# Super_iO_board.net
KiCad netlist of a schematic drawn in EAGLE
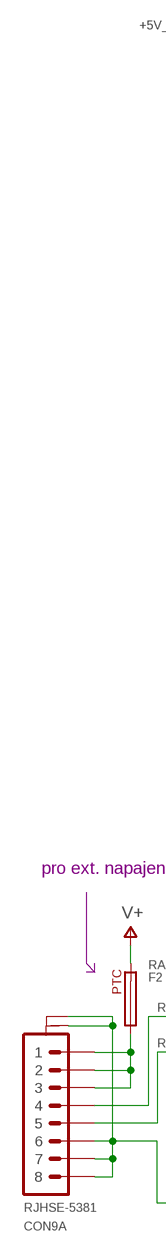
[diagram p0: schematic, sheet 1, part 1 of 2]
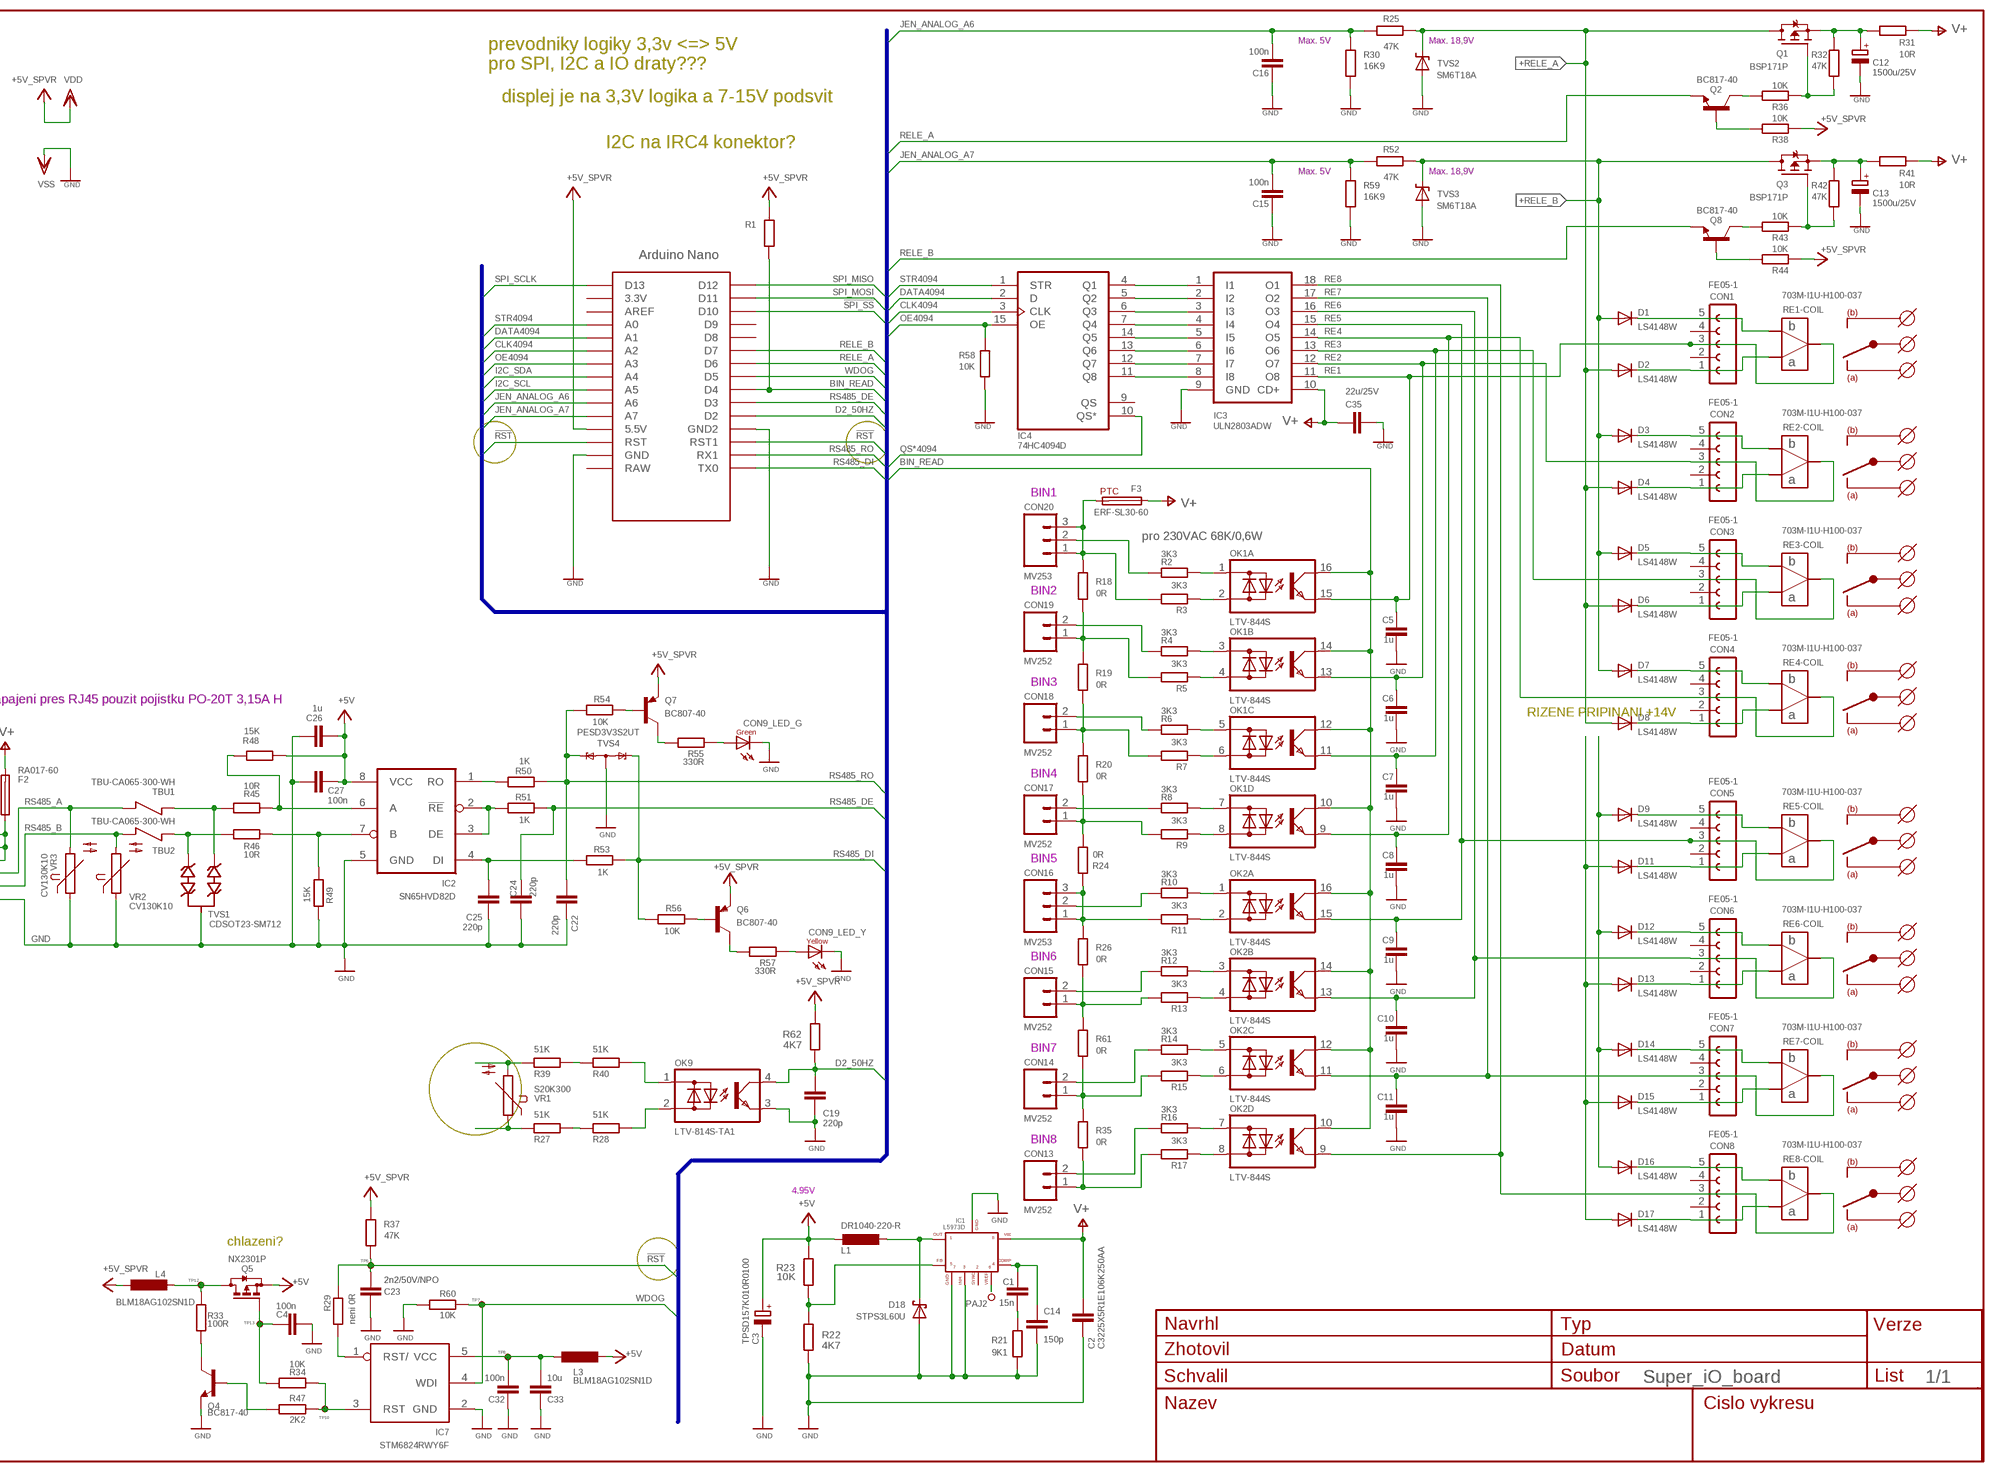
[diagram p1: schematic, sheet 1, part 2 of 2]

(export (version "E")
  (design (tool "Eeschema 10.0.6"))
  (components
    (comp (ref "C1")
      (value "15n")
      (footprint "eagle-import:C0805C")
      (libsource (lib "eagle-import") (part "C_EU_C0805C"))
    )
    (comp (ref "C2")
      (value "C3225X5R1E106K250AA")
      (footprint "eagle-import:C1210")
      (libsource (lib "eagle-import") (part "C-EUC1210"))
    )
    (comp (ref "C3")
      (value "TPSD157K010R0100")
      (footprint "eagle-import:D_7343-31R")
      (libsource (lib "eagle-import") (part "CPOL-EUD/7343-31R"))
    )
    (comp (ref "C4")
      (value "100n")
      (footprint "eagle-import:C0805C-M")
      (libsource (lib "eagle-import") (part "C_EU_C0805C-M"))
    )
    (comp (ref "C5")
      (value "1u")
      (footprint "eagle-import:C0805C-M")
      (libsource (lib "eagle-import") (part "C_EU_C0805C-M"))
    )
    (comp (ref "C6")
      (value "1u")
      (footprint "eagle-import:C0805C-M")
      (libsource (lib "eagle-import") (part "C_EU_C0805C-M"))
    )
    (comp (ref "C7")
      (value "1u")
      (footprint "eagle-import:C0805C-M")
      (libsource (lib "eagle-import") (part "C_EU_C0805C-M"))
    )
    (comp (ref "C8")
      (value "1u")
      (footprint "eagle-import:C0805C-M")
      (libsource (lib "eagle-import") (part "C_EU_C0805C-M"))
    )
    (comp (ref "C9")
      (value "1u")
      (footprint "eagle-import:C0805C-M")
      (libsource (lib "eagle-import") (part "C_EU_C0805C-M"))
    )
    (comp (ref "C10")
      (value "1u")
      (footprint "eagle-import:C0805C-M")
      (libsource (lib "eagle-import") (part "C_EU_C0805C-M"))
    )
    (comp (ref "C11")
      (value "1u")
      (footprint "eagle-import:C0805C-M")
      (libsource (lib "eagle-import") (part "C_EU_C0805C-M"))
    )
    (comp (ref "C12")
      (value "1500u/25V")
      (footprint "eagle-import:E5-13")
      (libsource (lib "eagle-import") (part "CPOL-EUE5-13"))
    )
    (comp (ref "C13")
      (value "1500u/25V")
      (footprint "eagle-import:E5-13")
      (libsource (lib "eagle-import") (part "CPOL-EUE5-13"))
    )
    (comp (ref "C14")
      (value "150p")
      (footprint "eagle-import:C0805C")
      (libsource (lib "eagle-import") (part "C_EU_C0805C"))
    )
    (comp (ref "C15")
      (value "100n")
      (footprint "eagle-import:C0805C-M")
      (libsource (lib "eagle-import") (part "C_EU_C0805C-M"))
    )
    (comp (ref "C16")
      (value "100n")
      (footprint "eagle-import:C0805C-M")
      (libsource (lib "eagle-import") (part "C_EU_C0805C-M"))
    )
    (comp (ref "C19")
      (value "220p")
      (footprint "eagle-import:C0805C-M")
      (libsource (lib "eagle-import") (part "C_EU_C0805C-M"))
    )
    (comp (ref "C22")
      (value "220p")
      (footprint "eagle-import:C0805C-M")
      (libsource (lib "eagle-import") (part "C_EU_C0805C-M"))
    )
    (comp (ref "C23")
      (value "2n2/50V/NPO")
      (footprint "eagle-import:C0805C-M")
      (libsource (lib "eagle-import") (part "C_EU_C0805C-M"))
    )
    (comp (ref "C24")
      (value "220p")
      (footprint "eagle-import:C0805C-M")
      (libsource (lib "eagle-import") (part "C_EU_C0805C-M"))
    )
    (comp (ref "C25")
      (value "220p")
      (footprint "eagle-import:C0805C-M")
      (libsource (lib "eagle-import") (part "C_EU_C0805C-M"))
    )
    (comp (ref "C26")
      (value "1u")
      (footprint "eagle-import:C0805C-M")
      (libsource (lib "eagle-import") (part "C_EU_C0805C-M"))
    )
    (comp (ref "C27")
      (value "100n")
      (footprint "eagle-import:C0805C-M")
      (libsource (lib "eagle-import") (part "C_EU_C0805C-M"))
    )
    (comp (ref "C32")
      (value "100n")
      (footprint "eagle-import:C0805C-M")
      (libsource (lib "eagle-import") (part "C_EU_C0805C-M"))
    )
    (comp (ref "C33")
      (value "10u")
      (footprint "eagle-import:C0805C-M")
      (libsource (lib "eagle-import") (part "C_EU_C0805C-M"))
    )
    (comp (ref "C35")
      (value "22u/25V")
      (footprint "eagle-import:C1206")
      (libsource (lib "eagle-import") (part "C_EU_1206"))
    )
    (comp (ref "CON1")
      (value "FE05-1")
      (footprint "eagle-import:FE05-1")
      (libsource (lib "eagle-import") (part "FE05-1"))
    )
    (comp (ref "CON2")
      (value "FE05-1")
      (footprint "eagle-import:FE05-1")
      (libsource (lib "eagle-import") (part "FE05-1"))
    )
    (comp (ref "CON3")
      (value "FE05-1")
      (footprint "eagle-import:FE05-1")
      (libsource (lib "eagle-import") (part "FE05-1"))
    )
    (comp (ref "CON4")
      (value "FE05-1")
      (footprint "eagle-import:FE05-1")
      (libsource (lib "eagle-import") (part "FE05-1"))
    )
    (comp (ref "CON5")
      (value "FE05-1")
      (footprint "eagle-import:FE05-1")
      (libsource (lib "eagle-import") (part "FE05-1"))
    )
    (comp (ref "CON6")
      (value "FE05-1")
      (footprint "eagle-import:FE05-1")
      (libsource (lib "eagle-import") (part "FE05-1"))
    )
    (comp (ref "CON7")
      (value "FE05-1")
      (footprint "eagle-import:FE05-1")
      (libsource (lib "eagle-import") (part "FE05-1"))
    )
    (comp (ref "CON8")
      (value "FE05-1")
      (footprint "eagle-import:FE05-1")
      (libsource (lib "eagle-import") (part "FE05-1"))
    )
    (comp (ref "CON9")
      (value "RJHSE-5381")
      (footprint "eagle-import:RJHSE538X_PROKOVY")
      (libsource (lib "eagle-import") (part "RJHSE5381_PROKOVY"))
    )
    (comp (ref "CON13")
      (value "MV252")
      (footprint "eagle-import:MRT5_2_61010-1_KULATE")
      (libsource (lib "eagle-import") (part "MRT5_2_61010-1_KULATE"))
    )
    (comp (ref "CON14")
      (value "MV252")
      (footprint "eagle-import:MRT5_2_61010-1_KULATE")
      (libsource (lib "eagle-import") (part "MRT5_2_61010-1_KULATE"))
    )
    (comp (ref "CON15")
      (value "MV252")
      (footprint "eagle-import:MRT5_2_61010-1_KULATE")
      (libsource (lib "eagle-import") (part "MRT5_2_61010-1_KULATE"))
    )
    (comp (ref "CON16")
      (value "MV253")
      (footprint "eagle-import:MRT5_3_61010-1_KULATE")
      (libsource (lib "eagle-import") (part "MRT5_3_61010-1_KULATE"))
    )
    (comp (ref "CON17")
      (value "MV252")
      (footprint "eagle-import:MRT5_2_61010-1_KULATE")
      (libsource (lib "eagle-import") (part "MRT5_2_61010-1_KULATE"))
    )
    (comp (ref "CON18")
      (value "MV252")
      (footprint "eagle-import:MRT5_2_61010-1_KULATE")
      (libsource (lib "eagle-import") (part "MRT5_2_61010-1_KULATE"))
    )
    (comp (ref "CON19")
      (value "MV252")
      (footprint "eagle-import:MRT5_2_61010-1_KULATE")
      (libsource (lib "eagle-import") (part "MRT5_2_61010-1_KULATE"))
    )
    (comp (ref "CON20")
      (value "MV253")
      (footprint "eagle-import:MRT5_3_61010-1_KULATE")
      (libsource (lib "eagle-import") (part "MRT5_3_61010-1_KULATE"))
    )
    (comp (ref "D1")
      (value "LS4148W")
      (footprint "eagle-import:D1206")
      (libsource (lib "eagle-import") (part "1N41481206"))
    )
    (comp (ref "D2")
      (value "LS4148W")
      (footprint "eagle-import:D1206")
      (libsource (lib "eagle-import") (part "1N41481206"))
    )
    (comp (ref "D3")
      (value "LS4148W")
      (footprint "eagle-import:D1206")
      (libsource (lib "eagle-import") (part "1N41481206"))
    )
    (comp (ref "D4")
      (value "LS4148W")
      (footprint "eagle-import:D1206")
      (libsource (lib "eagle-import") (part "1N41481206"))
    )
    (comp (ref "D5")
      (value "LS4148W")
      (footprint "eagle-import:D1206")
      (libsource (lib "eagle-import") (part "1N41481206"))
    )
    (comp (ref "D6")
      (value "LS4148W")
      (footprint "eagle-import:D1206")
      (libsource (lib "eagle-import") (part "1N41481206"))
    )
    (comp (ref "D7")
      (value "LS4148W")
      (footprint "eagle-import:D1206")
      (libsource (lib "eagle-import") (part "1N41481206"))
    )
    (comp (ref "D8")
      (value "LS4148W")
      (footprint "eagle-import:D1206")
      (libsource (lib "eagle-import") (part "1N41481206"))
    )
    (comp (ref "D9")
      (value "LS4148W")
      (footprint "eagle-import:D1206")
      (libsource (lib "eagle-import") (part "1N41481206"))
    )
    (comp (ref "D11")
      (value "LS4148W")
      (footprint "eagle-import:D1206")
      (libsource (lib "eagle-import") (part "1N41481206"))
    )
    (comp (ref "D12")
      (value "LS4148W")
      (footprint "eagle-import:D1206")
      (libsource (lib "eagle-import") (part "1N41481206"))
    )
    (comp (ref "D13")
      (value "LS4148W")
      (footprint "eagle-import:D1206")
      (libsource (lib "eagle-import") (part "1N41481206"))
    )
    (comp (ref "D14")
      (value "LS4148W")
      (footprint "eagle-import:D1206")
      (libsource (lib "eagle-import") (part "1N41481206"))
    )
    (comp (ref "D15")
      (value "LS4148W")
      (footprint "eagle-import:D1206")
      (libsource (lib "eagle-import") (part "1N41481206"))
    )
    (comp (ref "D16")
      (value "LS4148W")
      (footprint "eagle-import:D1206")
      (libsource (lib "eagle-import") (part "1N41481206"))
    )
    (comp (ref "D17")
      (value "LS4148W")
      (footprint "eagle-import:D1206")
      (libsource (lib "eagle-import") (part "1N41481206"))
    )
    (comp (ref "D18")
      (value "STPS3L60U")
      (footprint "eagle-import:SMB")
      (libsource (lib "eagle-import") (part "SCHOTTKY-DIODESMD"))
    )
    (comp (ref "F2")
      (value "RA017-60")
      (footprint "eagle-import:ERF-RA01760Z")
      (libsource (lib "eagle-import") (part "RA017-60017-60"))
    )
    (comp (ref "F3")
      (value "ERF-SL30-60")
      (footprint "eagle-import:ERF-SL030")
      (libsource (lib "eagle-import") (part "ERF-SL030-60"))
    )
    (comp (ref "IC1")
      (value "L5973D")
      (footprint "eagle-import:HSOP8")
      (libsource (lib "eagle-import") (part "L5973D"))
    )
    (comp (ref "IC2")
      (value "SN65HVD82D")
      (footprint "eagle-import:SO8_IPC_LEPIDLO")
      (libsource (lib "eagle-import") (part "ISL8487LEPIDLO"))
    )
    (comp (ref "IC3")
      (value "ULN2803ADW")
      (footprint "eagle-import:SO18W")
      (libsource (lib "eagle-import") (part "ULN2803ASMD"))
    )
    (comp (ref "IC4")
      (value "74HC4094D")
      (footprint "eagle-import:SO16")
      (libsource (lib "eagle-import") (part "4094D"))
    )
    (comp (ref "IC7")
      (value "STM6824RWY6F")
      (footprint "eagle-import:SOT23-5L")
      (libsource (lib "eagle-import") (part "STM6824SOT23-5L"))
    )
    (comp (ref "L1")
      (value "DR1040-220-R")
      (footprint "eagle-import:DR1040_RUCNE")
      (libsource (lib "eagle-import") (part "L-EUDR1040_RUCNE"))
    )
    (comp (ref "L3")
      (value "BLM18AG102SN1D")
      (footprint "eagle-import:L0603")
      (libsource (lib "eagle-import") (part "L-EUL0603"))
    )
    (comp (ref "L4")
      (value "BLM18AG102SN1D")
      (footprint "eagle-import:L0603")
      (libsource (lib "eagle-import") (part "L-EUL0603"))
    )
    (comp (ref "OK1")
      (value "LTV-844S")
      (footprint "eagle-import:SOIC254P1016X380-16N")
      (libsource (lib "eagle-import") (part "LTV-844S"))
    )
    (comp (ref "OK2")
      (value "LTV-844S")
      (footprint "eagle-import:SOIC254P1016X380-16N")
      (libsource (lib "eagle-import") (part "LTV-844S"))
    )
    (comp (ref "OK9")
      (value "LTV-814S-TA1")
      (footprint "eagle-import:SMD4-7_PLOSKY")
      (libsource (lib "eagle-import") (part "PC814SMD4-7_PLOSKY"))
    )
    (comp (ref "PAJ2")
      (value "PBM")
      (footprint "eagle-import:MER_BOD1MM")
      (libsource (lib "eagle-import") (part "MER_BOS11MM"))
    )
    (comp (ref "Q1")
      (value "BSP171P")
      (footprint "eagle-import:SOT223")
      (libsource (lib "eagle-import") (part "BSP170P"))
    )
    (comp (ref "Q2")
      (value "BC817-40")
      (footprint "eagle-import:SOT23_VLNA")
      (libsource (lib "eagle-import") (part "BC817VLNA"))
    )
    (comp (ref "Q3")
      (value "BSP171P")
      (footprint "eagle-import:SOT223")
      (libsource (lib "eagle-import") (part "BSP170P"))
    )
    (comp (ref "Q4")
      (value "BC817-40")
      (footprint "eagle-import:SOT23_VLNA")
      (libsource (lib "eagle-import") (part "BC817VLNA"))
    )
    (comp (ref "Q5")
      (value "NX2301P")
      (footprint "eagle-import:SOT23_VLNA")
      (libsource (lib "eagle-import") (part "BSS84VLNA"))
    )
    (comp (ref "Q6")
      (value "BC807-40")
      (footprint "eagle-import:SOT23BEC_VLNA")
      (libsource (lib "eagle-import") (part "BC807VLNA"))
    )
    (comp (ref "Q7")
      (value "BC807-40")
      (footprint "eagle-import:SOT23BEC_VLNA")
      (libsource (lib "eagle-import") (part "BC807VLNA"))
    )
    (comp (ref "Q8")
      (value "BC817-40")
      (footprint "eagle-import:SOT23_VLNA")
      (libsource (lib "eagle-import") (part "BC817VLNA"))
    )
    (comp (ref "R1")
      (value "R_EU_R1206-M")
      (footprint "eagle-import:RC1206N-M")
      (libsource (lib "eagle-import") (part "R_EU_R1206-M"))
    )
    (comp (ref "R2")
      (value "3K3")
      (footprint "eagle-import:0207_8.5+1206")
      (libsource (lib "eagle-import") (part "R-EU_0207/8.5+1206"))
    )
    (comp (ref "R3")
      (value "3K3")
      (footprint "eagle-import:0207_8.5+1206")
      (libsource (lib "eagle-import") (part "R-EU_0207/8.5+1206"))
    )
    (comp (ref "R4")
      (value "3K3")
      (footprint "eagle-import:0207_8.5+1206")
      (libsource (lib "eagle-import") (part "R-EU_0207/8.5+1206"))
    )
    (comp (ref "R5")
      (value "3K3")
      (footprint "eagle-import:0207_8.5+1206")
      (libsource (lib "eagle-import") (part "R-EU_0207/8.5+1206"))
    )
    (comp (ref "R6")
      (value "3K3")
      (footprint "eagle-import:0207_8.5+1206")
      (libsource (lib "eagle-import") (part "R-EU_0207/8.5+1206"))
    )
    (comp (ref "R7")
      (value "3K3")
      (footprint "eagle-import:0207_8.5+1206")
      (libsource (lib "eagle-import") (part "R-EU_0207/8.5+1206"))
    )
    (comp (ref "R8")
      (value "3K3")
      (footprint "eagle-import:0207_8.5+1206")
      (libsource (lib "eagle-import") (part "R-EU_0207/8.5+1206"))
    )
    (comp (ref "R9")
      (value "3K3")
      (footprint "eagle-import:0207_8.5+1206")
      (libsource (lib "eagle-import") (part "R-EU_0207/8.5+1206"))
    )
    (comp (ref "R10")
      (value "3K3")
      (footprint "eagle-import:0207_8.5+1206")
      (libsource (lib "eagle-import") (part "R-EU_0207/8.5+1206"))
    )
    (comp (ref "R11")
      (value "3K3")
      (footprint "eagle-import:0207_8.5+1206")
      (libsource (lib "eagle-import") (part "R-EU_0207/8.5+1206"))
    )
    (comp (ref "R12")
      (value "3K3")
      (footprint "eagle-import:0207_8.5+1206")
      (libsource (lib "eagle-import") (part "R-EU_0207/8.5+1206"))
    )
    (comp (ref "R13")
      (value "3K3")
      (footprint "eagle-import:0207_8.5+1206")
      (libsource (lib "eagle-import") (part "R-EU_0207/8.5+1206"))
    )
    (comp (ref "R14")
      (value "3K3")
      (footprint "eagle-import:0207_8.5+1206")
      (libsource (lib "eagle-import") (part "R-EU_0207/8.5+1206"))
    )
    (comp (ref "R15")
      (value "3K3")
      (footprint "eagle-import:0207_8.5+1206")
      (libsource (lib "eagle-import") (part "R-EU_0207/8.5+1206"))
    )
    (comp (ref "R16")
      (value "3K3")
      (footprint "eagle-import:0207_8.5+1206")
      (libsource (lib "eagle-import") (part "R-EU_0207/8.5+1206"))
    )
    (comp (ref "R17")
      (value "3K3")
      (footprint "eagle-import:0207_8.5+1206")
      (libsource (lib "eagle-import") (part "R-EU_0207/8.5+1206"))
    )
    (comp (ref "R18")
      (value "0R")
      (footprint "eagle-import:R2512")
      (libsource (lib "eagle-import") (part "R-EU_R2512"))
    )
    (comp (ref "R19")
      (value "0R")
      (footprint "eagle-import:R2512")
      (libsource (lib "eagle-import") (part "R-EU_R2512"))
    )
    (comp (ref "R20")
      (value "0R")
      (footprint "eagle-import:R2512")
      (libsource (lib "eagle-import") (part "R-EU_R2512"))
    )
    (comp (ref "R21")
      (value "9K1")
      (footprint "eagle-import:YAG_R0805-M")
      (libsource (lib "eagle-import") (part "R_EU_R0805-M"))
    )
    (comp (ref "R22")
      (value "4K7")
      (footprint "eagle-import:YAG_R0805-M")
      (libsource (lib "eagle-import") (part "R_EU_R0805-M"))
    )
    (comp (ref "R23")
      (value "10K")
      (footprint "eagle-import:YAG_R0805-M")
      (libsource (lib "eagle-import") (part "R_EU_R0805-M"))
    )
    (comp (ref "R24")
      (value "0R")
      (footprint "eagle-import:0207_7")
      (libsource (lib "eagle-import") (part "R-EU_0207/7"))
    )
    (comp (ref "R25")
      (value "47K")
      (footprint "eagle-import:YAG_R0805-M")
      (libsource (lib "eagle-import") (part "R_EU_R0805-M"))
    )
    (comp (ref "R26")
      (value "0R")
      (footprint "eagle-import:R2512")
      (libsource (lib "eagle-import") (part "R-EU_R2512"))
    )
    (comp (ref "R27")
      (value "51K")
      (footprint "eagle-import:RC1206N-M")
      (libsource (lib "eagle-import") (part "R_EU_R1206-M"))
    )
    (comp (ref "R28")
      (value "51K")
      (footprint "eagle-import:RC1206N-M")
      (libsource (lib "eagle-import") (part "R_EU_R1206-M"))
    )
    (comp (ref "R29")
      (value "neni 0R")
      (footprint "eagle-import:YAG_R0805-M")
      (libsource (lib "eagle-import") (part "R_EU_R0805-M"))
    )
    (comp (ref "R30")
      (value "16K9")
      (footprint "eagle-import:YAG_R0805-M")
      (libsource (lib "eagle-import") (part "R_EU_R0805-M"))
    )
    (comp (ref "R31")
      (value "10R")
      (footprint "eagle-import:R2010")
      (libsource (lib "eagle-import") (part "R-EU_R2010"))
    )
    (comp (ref "R32")
      (value "47K")
      (footprint "eagle-import:YAG_R0805-M")
      (libsource (lib "eagle-import") (part "R_EU_R0805-M"))
    )
    (comp (ref "R33")
      (value "100R")
      (footprint "eagle-import:RC1206N-M")
      (libsource (lib "eagle-import") (part "R_EU_R1206-M"))
    )
    (comp (ref "R34")
      (value "10K")
      (footprint "eagle-import:YAG_R0805-M")
      (libsource (lib "eagle-import") (part "R_EU_R0805-M"))
    )
    (comp (ref "R35")
      (value "0R")
      (footprint "eagle-import:R2512")
      (libsource (lib "eagle-import") (part "R-EU_R2512"))
    )
    (comp (ref "R36")
      (value "10K")
      (footprint "eagle-import:YAG_R0805-M")
      (libsource (lib "eagle-import") (part "R_EU_R0805-M"))
    )
    (comp (ref "R37")
      (value "47K")
      (footprint "eagle-import:YAG_R0805-M")
      (libsource (lib "eagle-import") (part "R_EU_R0805-M"))
    )
    (comp (ref "R38")
      (value "10K")
      (footprint "eagle-import:YAG_R0805-M")
      (libsource (lib "eagle-import") (part "R_EU_R0805-M"))
    )
    (comp (ref "R39")
      (value "51K")
      (footprint "eagle-import:RC1206N-M")
      (libsource (lib "eagle-import") (part "R_EU_R1206-M"))
    )
    (comp (ref "R40")
      (value "51K")
      (footprint "eagle-import:RC1206N-M")
      (libsource (lib "eagle-import") (part "R_EU_R1206-M"))
    )
    (comp (ref "R41")
      (value "10R")
      (footprint "eagle-import:R2010")
      (libsource (lib "eagle-import") (part "R-EU_R2010"))
    )
    (comp (ref "R42")
      (value "47K")
      (footprint "eagle-import:YAG_R0805-M")
      (libsource (lib "eagle-import") (part "R_EU_R0805-M"))
    )
    (comp (ref "R43")
      (value "10K")
      (footprint "eagle-import:YAG_R0805-M")
      (libsource (lib "eagle-import") (part "R_EU_R0805-M"))
    )
    (comp (ref "R44")
      (value "10K")
      (footprint "eagle-import:YAG_R0805-M")
      (libsource (lib "eagle-import") (part "R_EU_R0805-M"))
    )
    (comp (ref "R45")
      (value "10R")
      (footprint "eagle-import:R2010")
      (libsource (lib "eagle-import") (part "R-EU_R2010"))
    )
    (comp (ref "R46")
      (value "10R")
      (footprint "eagle-import:R2010")
      (libsource (lib "eagle-import") (part "R-EU_R2010"))
    )
    (comp (ref "R47")
      (value "2K2")
      (footprint "eagle-import:YAG_R0805-M")
      (libsource (lib "eagle-import") (part "R_EU_R0805-M"))
    )
    (comp (ref "R48")
      (value "15K")
      (footprint "eagle-import:R1206")
      (libsource (lib "eagle-import") (part "R-EU_R1206"))
    )
    (comp (ref "R49")
      (value "15K")
      (footprint "eagle-import:R1206")
      (libsource (lib "eagle-import") (part "R-EU_R1206"))
    )
    (comp (ref "R50")
      (value "1K")
      (footprint "eagle-import:R0805")
      (libsource (lib "eagle-import") (part "R-EU_R0805"))
    )
    (comp (ref "R51")
      (value "1K")
      (footprint "eagle-import:R0805")
      (libsource (lib "eagle-import") (part "R-EU_R0805"))
    )
    (comp (ref "R52")
      (value "47K")
      (footprint "eagle-import:YAG_R0805-M")
      (libsource (lib "eagle-import") (part "R_EU_R0805-M"))
    )
    (comp (ref "R53")
      (value "1K")
      (footprint "eagle-import:R0805")
      (libsource (lib "eagle-import") (part "R-EU_R0805"))
    )
    (comp (ref "R54")
      (value "10K")
      (footprint "eagle-import:YAG_R0805-M")
      (libsource (lib "eagle-import") (part "R_EU_R0805-M"))
    )
    (comp (ref "R55")
      (value "330R")
      (footprint "eagle-import:R0805")
      (libsource (lib "eagle-import") (part "R-EU_R0805"))
    )
    (comp (ref "R56")
      (value "10K")
      (footprint "eagle-import:YAG_R0805-M")
      (libsource (lib "eagle-import") (part "R_EU_R0805-M"))
    )
    (comp (ref "R57")
      (value "330R")
      (footprint "eagle-import:R0805")
      (libsource (lib "eagle-import") (part "R-EU_R0805"))
    )
    (comp (ref "R58")
      (value "10K")
      (footprint "eagle-import:YAG_R0805-M")
      (libsource (lib "eagle-import") (part "R_EU_R0805-M"))
    )
    (comp (ref "R59")
      (value "16K9")
      (footprint "eagle-import:YAG_R0805-M")
      (libsource (lib "eagle-import") (part "R_EU_R0805-M"))
    )
    (comp (ref "R60")
      (value "10K")
      (footprint "eagle-import:YAG_R0805-M")
      (libsource (lib "eagle-import") (part "R_EU_R0805-M"))
    )
    (comp (ref "R61")
      (value "0R")
      (footprint "eagle-import:R2512")
      (libsource (lib "eagle-import") (part "R-EU_R2512"))
    )
    (comp (ref "R62")
      (value "4K7")
      (footprint "eagle-import:YAG_R0805-M")
      (libsource (lib "eagle-import") (part "R_EU_R0805-M"))
    )
    (comp (ref "RE1")
      (value "703M-I1U-H100-037")
      (footprint "eagle-import:RELE_703_M-NOPIN")
      (libsource (lib "eagle-import") (part "703M-NOPIN"))
    )
    (comp (ref "RE2")
      (value "703M-I1U-H100-037")
      (footprint "eagle-import:RELE_703_M-NOPIN")
      (libsource (lib "eagle-import") (part "703M-NOPIN"))
    )
    (comp (ref "RE3")
      (value "703M-I1U-H100-037")
      (footprint "eagle-import:RELE_703_M-NOPIN")
      (libsource (lib "eagle-import") (part "703M-NOPIN"))
    )
    (comp (ref "RE4")
      (value "703M-I1U-H100-037")
      (footprint "eagle-import:RELE_703_M-NOPIN")
      (libsource (lib "eagle-import") (part "703M-NOPIN"))
    )
    (comp (ref "RE5")
      (value "703M-I1U-H100-037")
      (footprint "eagle-import:RELE_703_M-NOPIN")
      (libsource (lib "eagle-import") (part "703M-NOPIN"))
    )
    (comp (ref "RE6")
      (value "703M-I1U-H100-037")
      (footprint "eagle-import:RELE_703_M-NOPIN")
      (libsource (lib "eagle-import") (part "703M-NOPIN"))
    )
    (comp (ref "RE7")
      (value "703M-I1U-H100-037")
      (footprint "eagle-import:RELE_703_M-NOPIN")
      (libsource (lib "eagle-import") (part "703M-NOPIN"))
    )
    (comp (ref "RE8")
      (value "703M-I1U-H100-037")
      (footprint "eagle-import:RELE_703_M-NOPIN")
      (libsource (lib "eagle-import") (part "703M-NOPIN"))
    )
    (comp (ref "TBU1")
      (value "TBU-CA065-300-WH")
      (footprint "eagle-import:TBU-CA")
      (libsource (lib "eagle-import") (part "TBU-CA"))
    )
    (comp (ref "TBU2")
      (value "TBU-CA065-300-WH")
      (footprint "eagle-import:TBU-CA")
      (libsource (lib "eagle-import") (part "TBU-CA"))
    )
    (comp (ref "TP6")
      (value "MER_BOD_1MM_PRUBEH")
      (footprint "eagle-import:MER_BOD_1MM")
      (libsource (lib "eagle-import") (part "MER_BOD_1MM_PRUBEH"))
    )
    (comp (ref "TP7")
      (value "MER_BOD_1MM_PRUBEH")
      (footprint "eagle-import:MER_BOD_1MM")
      (libsource (lib "eagle-import") (part "MER_BOD_1MM_PRUBEH"))
    )
    (comp (ref "TP8")
      (value "MER_BOD_1MM_PRUBEH")
      (footprint "eagle-import:MER_BOD_1MM")
      (libsource (lib "eagle-import") (part "MER_BOD_1MM_PRUBEH"))
    )
    (comp (ref "TP10")
      (value "MER_BOD_1MM_PRUBEH")
      (footprint "eagle-import:MER_BOD_1MM")
      (libsource (lib "eagle-import") (part "MER_BOD_1MM_PRUBEH"))
    )
    (comp (ref "TP12")
      (value "MER_BOD_1MM_PRUBEH")
      (footprint "eagle-import:MER_BOD_1MM")
      (libsource (lib "eagle-import") (part "MER_BOD_1MM_PRUBEH"))
    )
    (comp (ref "TP13")
      (value "MER_BOD_1MM_PRUBEH")
      (footprint "eagle-import:MER_BOD_1MM")
      (libsource (lib "eagle-import") (part "MER_BOD_1MM_PRUBEH"))
    )
    (comp (ref "TVS1")
      (value "CDSOT23-SM712")
      (footprint "eagle-import:SOT23_VLNA")
      (libsource (lib "eagle-import") (part "CDSOT23-SM712"))
    )
    (comp (ref "TVS2")
      (value "SM6T18A")
      (footprint "eagle-import:SMBJ_POLARITA")
      (libsource (lib "eagle-import") (part "SUPPRESSOR-UNI"))
    )
    (comp (ref "TVS3")
      (value "SM6T18A")
      (footprint "eagle-import:SMBJ_POLARITA")
      (libsource (lib "eagle-import") (part "SUPPRESSOR-UNI"))
    )
    (comp (ref "TVS4")
      (value "PESD3V3S2UT")
      (footprint "eagle-import:SOT23_VLNA")
      (libsource (lib "eagle-import") (part "PESD3V3S2UT"))
    )
    (comp (ref "U$1")
      (value "NANO")
      (footprint "eagle-import:NANO")
      (libsource (lib "eagle-import") (part "NANO"))
    )
    (comp (ref "VR1")
      (value "S20K300")
      (footprint "eagle-import:S20K300")
      (libsource (lib "eagle-import") (part "S20K300"))
    )
    (comp (ref "VR2")
      (value "CV130K10")
      (footprint "eagle-import:S10K175")
      (libsource (lib "eagle-import") (part "S10K175"))
    )
    (comp (ref "VR3")
      (value "CV130K10")
      (footprint "eagle-import:S10K175")
      (libsource (lib "eagle-import") (part "S10K175"))
    )
  )
  (nets
    (net (code "1") (name "+5V") (class "Default")
      (node (ref "C26") (pin "1") (pinfunction "1_1") (pintype "passive"))
      (node (ref "C27") (pin "1") (pinfunction "1_1") (pintype "passive"))
      (node (ref "C3") (pin "+") (pinfunction "+_+") (pintype "passive"))
      (node (ref "IC2") (pin "8") (pinfunction "VCC_8") (pintype "passive"))
      (node (ref "L1") (pin "2") (pinfunction "2_2") (pintype "passive"))
      (node (ref "L3") (pin "2") (pinfunction "2_2") (pintype "passive"))
      (node (ref "Q5") (pin "2") (pinfunction "S_2") (pintype "passive"))
      (node (ref "R23") (pin "2") (pinfunction "2_2") (pintype "passive"))
      (node (ref "R48") (pin "1") (pinfunction "1_1") (pintype "passive"))
    )
    (net (code "2") (name "+5V_SPVR") (class "Default")
      (node (ref "L4") (pin "1") (pinfunction "1_1") (pintype "passive"))
      (node (ref "Q6") (pin "E") (pinfunction "E_E") (pintype "passive"))
      (node (ref "Q7") (pin "E") (pinfunction "E_E") (pintype "passive"))
      (node (ref "R1") (pin "2") (pinfunction "2_2") (pintype "passive"))
      (node (ref "R37") (pin "2") (pinfunction "2_2") (pintype "passive"))
      (node (ref "R38") (pin "1") (pinfunction "1_1") (pintype "passive"))
      (node (ref "R44") (pin "1") (pinfunction "1_1") (pintype "passive"))
      (node (ref "R62") (pin "2") (pinfunction "2_2") (pintype "passive"))
      (node (ref "U$1") (pin "5V") (pinfunction "5.5V_5V") (pintype "bidirectional"))
    )
    (net (code "3") (name "+RELE_A") (class "Default")
      (node (ref "D2") (pin "A") (pinfunction "A_A") (pintype "passive"))
      (node (ref "D4") (pin "A") (pinfunction "A_A") (pintype "passive"))
      (node (ref "D6") (pin "A") (pinfunction "A_A") (pintype "passive"))
      (node (ref "D8") (pin "A") (pinfunction "A_A") (pintype "passive"))
      (node (ref "Q1") (pin "2") (pinfunction "D_2") (pintype "passive"))
      (node (ref "Q1") (pin "4") (pinfunction "D_4") (pintype "passive"))
      (node (ref "R25") (pin "2") (pinfunction "2_2") (pintype "passive"))
      (node (ref "TVS2") (pin "C") (pinfunction "C_C") (pintype "passive"))
    )
    (net (code "4") (name "+RELE_B") (class "Default")
      (node (ref "D1") (pin "A") (pinfunction "A_A") (pintype "passive"))
      (node (ref "D3") (pin "A") (pinfunction "A_A") (pintype "passive"))
      (node (ref "D5") (pin "A") (pinfunction "A_A") (pintype "passive"))
      (node (ref "D7") (pin "A") (pinfunction "A_A") (pintype "passive"))
      (node (ref "Q3") (pin "2") (pinfunction "D_2") (pintype "passive"))
      (node (ref "Q3") (pin "4") (pinfunction "D_4") (pintype "passive"))
      (node (ref "R52") (pin "2") (pinfunction "2_2") (pintype "passive"))
      (node (ref "TVS3") (pin "C") (pinfunction "C_C") (pintype "passive"))
    )
    (net (code "5") (name "/BIN_READ") (class "Default")
      (node (ref "OK1") (pin "10") (pinfunction "C_10") (pintype "passive"))
      (node (ref "OK1") (pin "12") (pinfunction "C_12") (pintype "passive"))
      (node (ref "OK1") (pin "14") (pinfunction "C_14") (pintype "passive"))
      (node (ref "OK1") (pin "16") (pinfunction "C_16") (pintype "passive"))
      (node (ref "OK2") (pin "10") (pinfunction "C_10") (pintype "passive"))
      (node (ref "OK2") (pin "12") (pinfunction "C_12") (pintype "passive"))
      (node (ref "OK2") (pin "14") (pinfunction "C_14") (pintype "passive"))
      (node (ref "OK2") (pin "16") (pinfunction "C_16") (pintype "passive"))
      (node (ref "R1") (pin "1") (pinfunction "1_1") (pintype "passive"))
      (node (ref "U$1") (pin "D4") (pinfunction "D4_D4") (pintype "bidirectional"))
    )
    (net (code "6") (name "/CLK4094") (class "Default")
      (node (ref "IC4") (pin "3") (pinfunction "CLK_3") (pintype "input"))
      (node (ref "U$1") (pin "A2") (pinfunction "A2_A2") (pintype "bidirectional"))
    )
    (net (code "7") (name "/D2_50HZ") (class "Default")
      (node (ref "C19") (pin "1") (pinfunction "1_1") (pintype "passive"))
      (node (ref "OK9") (pin "4") (pinfunction "C_4") (pintype "passive"))
      (node (ref "R62") (pin "1") (pinfunction "1_1") (pintype "passive"))
      (node (ref "U$1") (pin "D2") (pinfunction "D2_D2") (pintype "bidirectional"))
    )
    (net (code "8") (name "/DATA4094") (class "Default")
      (node (ref "IC4") (pin "2") (pinfunction "D_2") (pintype "input"))
      (node (ref "U$1") (pin "A1") (pinfunction "A1_A1") (pintype "bidirectional"))
    )
    (net (code "9") (name "/I2C_SCL") (class "Default")
      (node (ref "U$1") (pin "A5") (pinfunction "A5_A5") (pintype "bidirectional"))
    )
    (net (code "10") (name "/I2C_SDA") (class "Default")
      (node (ref "U$1") (pin "A4") (pinfunction "A4_A4") (pintype "bidirectional"))
    )
    (net (code "11") (name "/JEN_ANALOG_A6") (class "Default")
      (node (ref "C16") (pin "2") (pinfunction "2_2") (pintype "passive"))
      (node (ref "R25") (pin "1") (pinfunction "1_1") (pintype "passive"))
      (node (ref "R30") (pin "2") (pinfunction "2_2") (pintype "passive"))
      (node (ref "U$1") (pin "A6") (pinfunction "A6_A6") (pintype "bidirectional"))
    )
    (net (code "12") (name "/JEN_ANALOG_A7") (class "Default")
      (node (ref "C15") (pin "2") (pinfunction "2_2") (pintype "passive"))
      (node (ref "R52") (pin "1") (pinfunction "1_1") (pintype "passive"))
      (node (ref "R59") (pin "2") (pinfunction "2_2") (pintype "passive"))
      (node (ref "U$1") (pin "A7") (pinfunction "A7_A7") (pintype "bidirectional"))
    )
    (net (code "13") (name "/OE4094") (class "Default")
      (node (ref "IC4") (pin "15") (pinfunction "OE_15") (pintype "input"))
      (node (ref "R58") (pin "1") (pinfunction "1_1") (pintype "passive"))
      (node (ref "U$1") (pin "A3") (pinfunction "A3_A3") (pintype "bidirectional"))
    )
    (net (code "14") (name "/QS*4094") (class "Default")
      (node (ref "IC4") (pin "10") (pinfunction "QS*_10") (pintype "output"))
    )
    (net (code "15") (name "/RE1") (class "Default")
      (node (ref "C5") (pin "1") (pinfunction "1_1") (pintype "passive"))
      (node (ref "CON1") (pin "3") (pinfunction "3_3") (pintype "passive"))
      (node (ref "IC3") (pin "11") (pinfunction "O8_11") (pintype "open_collector"))
      (node (ref "OK1") (pin "15") (pinfunction "E_15") (pintype "passive"))
    )
    (net (code "16") (name "/RE2") (class "Default")
      (node (ref "C6") (pin "1") (pinfunction "1_1") (pintype "passive"))
      (node (ref "CON2") (pin "3") (pinfunction "3_3") (pintype "passive"))
      (node (ref "IC3") (pin "12") (pinfunction "O7_12") (pintype "open_collector"))
      (node (ref "OK1") (pin "13") (pinfunction "E_13") (pintype "passive"))
    )
    (net (code "17") (name "/RE3") (class "Default")
      (node (ref "C7") (pin "1") (pinfunction "1_1") (pintype "passive"))
      (node (ref "CON3") (pin "3") (pinfunction "3_3") (pintype "passive"))
      (node (ref "IC3") (pin "13") (pinfunction "O6_13") (pintype "open_collector"))
      (node (ref "OK1") (pin "11") (pinfunction "E_11") (pintype "passive"))
    )
    (net (code "18") (name "/RE4") (class "Default")
      (node (ref "C8") (pin "1") (pinfunction "1_1") (pintype "passive"))
      (node (ref "CON4") (pin "3") (pinfunction "3_3") (pintype "passive"))
      (node (ref "IC3") (pin "14") (pinfunction "O5_14") (pintype "open_collector"))
      (node (ref "OK1") (pin "9") (pinfunction "E_9") (pintype "passive"))
    )
    (net (code "19") (name "/RE5") (class "Default")
      (node (ref "C9") (pin "1") (pinfunction "1_1") (pintype "passive"))
      (node (ref "CON5") (pin "3") (pinfunction "3_3") (pintype "passive"))
      (node (ref "IC3") (pin "15") (pinfunction "O4_15") (pintype "open_collector"))
      (node (ref "OK2") (pin "15") (pinfunction "E_15") (pintype "passive"))
    )
    (net (code "20") (name "/RE6") (class "Default")
      (node (ref "C10") (pin "1") (pinfunction "1_1") (pintype "passive"))
      (node (ref "CON6") (pin "3") (pinfunction "3_3") (pintype "passive"))
      (node (ref "IC3") (pin "16") (pinfunction "O3_16") (pintype "open_collector"))
      (node (ref "OK2") (pin "13") (pinfunction "E_13") (pintype "passive"))
    )
    (net (code "21") (name "/RE7") (class "Default")
      (node (ref "C11") (pin "1") (pinfunction "1_1") (pintype "passive"))
      (node (ref "CON7") (pin "3") (pinfunction "3_3") (pintype "passive"))
      (node (ref "IC3") (pin "17") (pinfunction "O2_17") (pintype "open_collector"))
      (node (ref "OK2") (pin "11") (pinfunction "E_11") (pintype "passive"))
    )
    (net (code "22") (name "/RE8") (class "Default")
      (node (ref "CON8") (pin "3") (pinfunction "3_3") (pintype "passive"))
      (node (ref "IC3") (pin "18") (pinfunction "O1_18") (pintype "open_collector"))
      (node (ref "OK2") (pin "9") (pinfunction "E_9") (pintype "passive"))
    )
    (net (code "23") (name "/RELE_A") (class "Default")
      (node (ref "Q2") (pin "2") (pinfunction "E_2") (pintype "passive"))
      (node (ref "U$1") (pin "D6") (pinfunction "D6_D6") (pintype "bidirectional"))
    )
    (net (code "24") (name "/RELE_B") (class "Default")
      (node (ref "Q8") (pin "2") (pinfunction "E_2") (pintype "passive"))
      (node (ref "U$1") (pin "D7") (pinfunction "D7_D7") (pintype "bidirectional"))
    )
    (net (code "25") (name "/RS485_A") (class "Default")
      (node (ref "CON9") (pin "1_4") (pinfunction "4_1_4") (pintype "passive"))
      (node (ref "TBU1") (pin "2") (pinfunction "P$2_2") (pintype "passive"))
      (node (ref "VR3") (pin "2") (pinfunction "2_2") (pintype "passive"))
    )
    (net (code "26") (name "/RS485_B") (class "Default")
      (node (ref "CON9") (pin "1_5") (pinfunction "5_1_5") (pintype "passive"))
      (node (ref "TBU2") (pin "2") (pinfunction "P$2_2") (pintype "passive"))
      (node (ref "VR2") (pin "2") (pinfunction "2_2") (pintype "passive"))
    )
    (net (code "27") (name "/RS485_DE") (class "Default")
      (node (ref "C24") (pin "1") (pinfunction "1_1") (pintype "passive"))
      (node (ref "R51") (pin "2") (pinfunction "2_2") (pintype "passive"))
      (node (ref "U$1") (pin "D3") (pinfunction "D3_D3") (pintype "bidirectional"))
    )
    (net (code "28") (name "/RS485_DI") (class "Default")
      (node (ref "R53") (pin "2") (pinfunction "2_2") (pintype "passive"))
      (node (ref "R56") (pin "1") (pinfunction "1_1") (pintype "passive"))
      (node (ref "TVS4") (pin "2") (pinfunction "K2_2") (pintype "passive"))
      (node (ref "U$1") (pin "TX0") (pinfunction "TX0_TX0") (pintype "bidirectional"))
    )
    (net (code "29") (name "/RS485_RO") (class "Default")
      (node (ref "C22") (pin "1") (pinfunction "1_1") (pintype "passive"))
      (node (ref "R50") (pin "2") (pinfunction "2_2") (pintype "passive"))
      (node (ref "R54") (pin "1") (pinfunction "1_1") (pintype "passive"))
      (node (ref "TVS4") (pin "1") (pinfunction "K1_1") (pintype "passive"))
      (node (ref "U$1") (pin "RX1") (pinfunction "RX1_RX1") (pintype "bidirectional"))
    )
    (net (code "30") (name "/SPI_MISO") (class "Default")
      (node (ref "U$1") (pin "D12") (pinfunction "D12_D12") (pintype "bidirectional"))
    )
    (net (code "31") (name "/SPI_MOSI") (class "Default")
      (node (ref "U$1") (pin "D11") (pinfunction "D11_D11") (pintype "bidirectional"))
    )
    (net (code "32") (name "/SPI_SCLK") (class "Default")
      (node (ref "U$1") (pin "D13") (pinfunction "D13_D13") (pintype "bidirectional"))
    )
    (net (code "33") (name "/STR4094") (class "Default")
      (node (ref "IC4") (pin "1") (pinfunction "STR_1") (pintype "input"))
      (node (ref "U$1") (pin "A0") (pinfunction "A0_A0") (pintype "bidirectional"))
    )
    (net (code "34") (name "/WDOG") (class "Default")
      (node (ref "IC7") (pin "4") (pinfunction "WDI_4") (pintype "input"))
      (node (ref "R60") (pin "1") (pinfunction "1_1") (pintype "passive"))
      (node (ref "TP7") (pin "MB") (pinfunction "1_MB") (pintype "passive"))
      (node (ref "U$1") (pin "D5") (pinfunction "D5_D5") (pintype "bidirectional"))
    )
    (net (code "35") (name "/~{RST}") (class "Default")
      (node (ref "C23") (pin "1") (pinfunction "1_1") (pintype "passive"))
      (node (ref "R29") (pin "2") (pinfunction "2_2") (pintype "passive"))
      (node (ref "R37") (pin "1") (pinfunction "1_1") (pintype "passive"))
      (node (ref "TP6") (pin "MB") (pinfunction "1_MB") (pintype "passive"))
      (node (ref "U$1") (pin "RST") (pinfunction "RST_RST") (pintype "bidirectional"))
      (node (ref "U$1") (pin "RST1") (pinfunction "RST1_RST1") (pintype "bidirectional"))
    )
    (net (code "36") (name "/~{SPI_SS}") (class "Default")
      (node (ref "U$1") (pin "D10") (pinfunction "D10_D10") (pintype "bidirectional"))
    )
    (net (code "37") (name "GND") (class "Default")
      (node (ref "C10") (pin "2") (pinfunction "2_2") (pintype "passive"))
      (node (ref "C11") (pin "2") (pinfunction "2_2") (pintype "passive"))
      (node (ref "C12") (pin "-") (pinfunction "-_-") (pintype "passive"))
      (node (ref "C13") (pin "-") (pinfunction "-_-") (pintype "passive"))
      (node (ref "C14") (pin "1") (pinfunction "1_1") (pintype "passive"))
      (node (ref "C15") (pin "1") (pinfunction "1_1") (pintype "passive"))
      (node (ref "C16") (pin "1") (pinfunction "1_1") (pintype "passive"))
      (node (ref "C19") (pin "2") (pinfunction "2_2") (pintype "passive"))
      (node (ref "C2") (pin "2") (pinfunction "2_2") (pintype "passive"))
      (node (ref "C22") (pin "2") (pinfunction "2_2") (pintype "passive"))
      (node (ref "C23") (pin "2") (pinfunction "2_2") (pintype "passive"))
      (node (ref "C24") (pin "2") (pinfunction "2_2") (pintype "passive"))
      (node (ref "C25") (pin "2") (pinfunction "2_2") (pintype "passive"))
      (node (ref "C26") (pin "2") (pinfunction "2_2") (pintype "passive"))
      (node (ref "C27") (pin "2") (pinfunction "2_2") (pintype "passive"))
      (node (ref "C3") (pin "-") (pinfunction "-_-") (pintype "passive"))
      (node (ref "C32") (pin "1") (pinfunction "1_1") (pintype "passive"))
      (node (ref "C33") (pin "1") (pinfunction "1_1") (pintype "passive"))
      (node (ref "C35") (pin "2") (pinfunction "2_2") (pintype "passive"))
      (node (ref "C4") (pin "1") (pinfunction "1_1") (pintype "passive"))
      (node (ref "C5") (pin "2") (pinfunction "2_2") (pintype "passive"))
      (node (ref "C6") (pin "2") (pinfunction "2_2") (pintype "passive"))
      (node (ref "C7") (pin "2") (pinfunction "2_2") (pintype "passive"))
      (node (ref "C8") (pin "2") (pinfunction "2_2") (pintype "passive"))
      (node (ref "C9") (pin "2") (pinfunction "2_2") (pintype "passive"))
      (node (ref "CON9") (pin "1_6") (pinfunction "6_1_6") (pintype "passive"))
      (node (ref "CON9") (pin "1_7") (pinfunction "7_1_7") (pintype "passive"))
      (node (ref "CON9") (pin "1_8") (pinfunction "8_1_8") (pintype "passive"))
      (node (ref "CON9") (pin "K1") (pinfunction "K_K1") (pintype "passive"))
      (node (ref "CON9") (pin "K2") (pinfunction "K_K2") (pintype "passive"))
      (node (ref "CON9") (pin "S") (pinfunction "S_S") (pintype "passive"))
      (node (ref "CON9") (pin "S1") (pinfunction "S1_S1") (pintype "passive"))
      (node (ref "D18") (pin "A") (pinfunction "A_A") (pintype "passive"))
      (node (ref "IC1") (pin "3") (pinfunction "INH_3") (pintype "passive"))
      (node (ref "IC1") (pin "7") (pinfunction "GND_7") (pintype "passive"))
      (node (ref "IC1") (pin "GND") (pinfunction "GND1_GND") (pintype "passive"))
      (node (ref "IC2") (pin "5") (pinfunction "GND_5") (pintype "passive"))
      (node (ref "IC3") (pin "9") (pinfunction "GND_9") (pintype "power_in"))
      (node (ref "IC7") (pin "2") (pinfunction "GND_2") (pintype "power_in"))
      (node (ref "OK9") (pin "3") (pinfunction "E_3") (pintype "passive"))
      (node (ref "Q4") (pin "2") (pinfunction "E_2") (pintype "passive"))
      (node (ref "R21") (pin "1") (pinfunction "1_1") (pintype "passive"))
      (node (ref "R22") (pin "1") (pinfunction "1_1") (pintype "passive"))
      (node (ref "R30") (pin "1") (pinfunction "1_1") (pintype "passive"))
      (node (ref "R49") (pin "2") (pinfunction "2_2") (pintype "passive"))
      (node (ref "R58") (pin "2") (pinfunction "2_2") (pintype "passive"))
      (node (ref "R59") (pin "1") (pinfunction "1_1") (pintype "passive"))
      (node (ref "R60") (pin "2") (pinfunction "2_2") (pintype "passive"))
      (node (ref "TVS1") (pin "3") (pinfunction "3_3") (pintype "passive"))
      (node (ref "TVS2") (pin "A") (pinfunction "A_A") (pintype "passive"))
      (node (ref "TVS3") (pin "A") (pinfunction "A_A") (pintype "passive"))
      (node (ref "TVS4") (pin "3") (pinfunction "AA_3") (pintype "passive"))
      (node (ref "U$1") (pin "GND") (pinfunction "GND_GND") (pintype "bidirectional"))
      (node (ref "U$1") (pin "GND1") (pinfunction "GND2_GND1") (pintype "bidirectional"))
      (node (ref "VR2") (pin "1") (pinfunction "1_1") (pintype "passive"))
      (node (ref "VR3") (pin "1") (pinfunction "1_1") (pintype "passive"))
    )
    (net (code "38") (name "Net-(C1-Pad1)") (class "Default")
      (node (ref "C1") (pin "1") (pinfunction "1_1") (pintype "passive"))
      (node (ref "R21") (pin "2") (pinfunction "2_2") (pintype "passive"))
    )
    (net (code "39") (name "Net-(CON9A-1)") (class "Default")
      (node (ref "CON9") (pin "1_1") (pinfunction "1_1_1") (pintype "passive"))
      (node (ref "CON9") (pin "1_2") (pinfunction "2_1_2") (pintype "passive"))
      (node (ref "CON9") (pin "1_3") (pinfunction "3_1_3") (pintype "passive"))
      (node (ref "F2") (pin "P$1") (pinfunction "1_P$1") (pintype "passive"))
    )
    (net (code "40") (name "Net-(CON9B-A)") (class "Default")
      (node (ref "CON9") (pin "A1") (pinfunction "A_A1") (pintype "passive"))
      (node (ref "R55") (pin "2") (pinfunction "2_2") (pintype "passive"))
    )
    (net (code "41") (name "Net-(CON9C-A)") (class "Default")
      (node (ref "CON9") (pin "A2") (pinfunction "A_A2") (pintype "passive"))
      (node (ref "R57") (pin "2") (pinfunction "2_2") (pintype "passive"))
    )
    (net (code "42") (name "Net-(CON13-Pad1)") (class "Default")
      (node (ref "CON13") (pin "1") (pinfunction "1_1") (pintype "passive"))
      (node (ref "R17") (pin "2") (pinfunction "2_2") (pintype "passive"))
      (node (ref "R17") (pin "22") (pinfunction "2_22") (pintype "passive"))
      (node (ref "R35") (pin "1") (pinfunction "1_1") (pintype "passive"))
    )
    (net (code "43") (name "Net-(CON13-Pad2)") (class "Default")
      (node (ref "CON13") (pin "2") (pinfunction "2_2") (pintype "passive"))
      (node (ref "R16") (pin "1") (pinfunction "1_1") (pintype "passive"))
      (node (ref "R16") (pin "11") (pinfunction "1_11") (pintype "passive"))
    )
    (net (code "44") (name "Net-(CON14-Pad1)") (class "Default")
      (node (ref "CON14") (pin "1") (pinfunction "1_1") (pintype "passive"))
      (node (ref "R15") (pin "2") (pinfunction "2_2") (pintype "passive"))
      (node (ref "R15") (pin "22") (pinfunction "2_22") (pintype "passive"))
      (node (ref "R35") (pin "2") (pinfunction "2_2") (pintype "passive"))
      (node (ref "R61") (pin "1") (pinfunction "1_1") (pintype "passive"))
    )
    (net (code "45") (name "Net-(CON14-Pad2)") (class "Default")
      (node (ref "CON14") (pin "2") (pinfunction "2_2") (pintype "passive"))
      (node (ref "R14") (pin "1") (pinfunction "1_1") (pintype "passive"))
      (node (ref "R14") (pin "11") (pinfunction "1_11") (pintype "passive"))
    )
    (net (code "46") (name "Net-(CON15-Pad1)") (class "Default")
      (node (ref "CON15") (pin "1") (pinfunction "1_1") (pintype "passive"))
      (node (ref "R13") (pin "2") (pinfunction "2_2") (pintype "passive"))
      (node (ref "R13") (pin "22") (pinfunction "2_22") (pintype "passive"))
      (node (ref "R26") (pin "1") (pinfunction "1_1") (pintype "passive"))
      (node (ref "R61") (pin "2") (pinfunction "2_2") (pintype "passive"))
    )
    (net (code "47") (name "Net-(CON15-Pad2)") (class "Default")
      (node (ref "CON15") (pin "2") (pinfunction "2_2") (pintype "passive"))
      (node (ref "R12") (pin "1") (pinfunction "1_1") (pintype "passive"))
      (node (ref "R12") (pin "11") (pinfunction "1_11") (pintype "passive"))
    )
    (net (code "48") (name "Net-(CON16-Pad1)") (class "Default")
      (node (ref "CON16") (pin "1") (pinfunction "1_1") (pintype "passive"))
      (node (ref "CON16") (pin "3") (pinfunction "3_3") (pintype "passive"))
      (node (ref "R11") (pin "2") (pinfunction "2_2") (pintype "passive"))
      (node (ref "R11") (pin "22") (pinfunction "2_22") (pintype "passive"))
      (node (ref "R24") (pin "1") (pinfunction "1_1") (pintype "passive"))
      (node (ref "R26") (pin "2") (pinfunction "2_2") (pintype "passive"))
    )
    (net (code "49") (name "Net-(CON16-Pad2)") (class "Default")
      (node (ref "CON16") (pin "2") (pinfunction "2_2") (pintype "passive"))
      (node (ref "R10") (pin "1") (pinfunction "1_1") (pintype "passive"))
      (node (ref "R10") (pin "11") (pinfunction "1_11") (pintype "passive"))
    )
    (net (code "50") (name "Net-(CON17-Pad1)") (class "Default")
      (node (ref "CON17") (pin "1") (pinfunction "1_1") (pintype "passive"))
      (node (ref "R20") (pin "1") (pinfunction "1_1") (pintype "passive"))
      (node (ref "R24") (pin "2") (pinfunction "2_2") (pintype "passive"))
      (node (ref "R9") (pin "2") (pinfunction "2_2") (pintype "passive"))
      (node (ref "R9") (pin "22") (pinfunction "2_22") (pintype "passive"))
    )
    (net (code "51") (name "Net-(CON17-Pad2)") (class "Default")
      (node (ref "CON17") (pin "2") (pinfunction "2_2") (pintype "passive"))
      (node (ref "R8") (pin "1") (pinfunction "1_1") (pintype "passive"))
      (node (ref "R8") (pin "11") (pinfunction "1_11") (pintype "passive"))
    )
    (net (code "52") (name "Net-(CON18-Pad1)") (class "Default")
      (node (ref "CON18") (pin "1") (pinfunction "1_1") (pintype "passive"))
      (node (ref "R19") (pin "1") (pinfunction "1_1") (pintype "passive"))
      (node (ref "R20") (pin "2") (pinfunction "2_2") (pintype "passive"))
      (node (ref "R7") (pin "2") (pinfunction "2_2") (pintype "passive"))
      (node (ref "R7") (pin "22") (pinfunction "2_22") (pintype "passive"))
    )
    (net (code "53") (name "Net-(CON18-Pad2)") (class "Default")
      (node (ref "CON18") (pin "2") (pinfunction "2_2") (pintype "passive"))
      (node (ref "R6") (pin "1") (pinfunction "1_1") (pintype "passive"))
      (node (ref "R6") (pin "11") (pinfunction "1_11") (pintype "passive"))
    )
    (net (code "54") (name "Net-(CON19-Pad1)") (class "Default")
      (node (ref "CON19") (pin "1") (pinfunction "1_1") (pintype "passive"))
      (node (ref "R18") (pin "1") (pinfunction "1_1") (pintype "passive"))
      (node (ref "R19") (pin "2") (pinfunction "2_2") (pintype "passive"))
      (node (ref "R5") (pin "2") (pinfunction "2_2") (pintype "passive"))
      (node (ref "R5") (pin "22") (pinfunction "2_22") (pintype "passive"))
    )
    (net (code "55") (name "Net-(CON19-Pad2)") (class "Default")
      (node (ref "CON19") (pin "2") (pinfunction "2_2") (pintype "passive"))
      (node (ref "R4") (pin "1") (pinfunction "1_1") (pintype "passive"))
      (node (ref "R4") (pin "11") (pinfunction "1_11") (pintype "passive"))
    )
    (net (code "56") (name "Net-(CON20-Pad2)") (class "Default")
      (node (ref "CON20") (pin "2") (pinfunction "2_2") (pintype "passive"))
      (node (ref "R2") (pin "1") (pinfunction "1_1") (pintype "passive"))
      (node (ref "R2") (pin "11") (pinfunction "1_11") (pintype "passive"))
    )
    (net (code "57") (name "Net-(D1-C)") (class "Default")
      (node (ref "CON1") (pin "5") (pinfunction "5_5") (pintype "passive"))
      (node (ref "D1") (pin "K") (pinfunction "C_K") (pintype "passive"))
    )
    (net (code "58") (name "Net-(D2-C)") (class "Default")
      (node (ref "CON1") (pin "1") (pinfunction "1_1") (pintype "passive"))
      (node (ref "D2") (pin "K") (pinfunction "C_K") (pintype "passive"))
    )
    (net (code "59") (name "Net-(D3-C)") (class "Default")
      (node (ref "CON2") (pin "5") (pinfunction "5_5") (pintype "passive"))
      (node (ref "D3") (pin "K") (pinfunction "C_K") (pintype "passive"))
    )
    (net (code "60") (name "Net-(D4-C)") (class "Default")
      (node (ref "CON2") (pin "1") (pinfunction "1_1") (pintype "passive"))
      (node (ref "D4") (pin "K") (pinfunction "C_K") (pintype "passive"))
    )
    (net (code "61") (name "Net-(D5-C)") (class "Default")
      (node (ref "CON3") (pin "5") (pinfunction "5_5") (pintype "passive"))
      (node (ref "D5") (pin "K") (pinfunction "C_K") (pintype "passive"))
    )
    (net (code "62") (name "Net-(D6-C)") (class "Default")
      (node (ref "CON3") (pin "1") (pinfunction "1_1") (pintype "passive"))
      (node (ref "D6") (pin "K") (pinfunction "C_K") (pintype "passive"))
    )
    (net (code "63") (name "Net-(D7-C)") (class "Default")
      (node (ref "CON4") (pin "5") (pinfunction "5_5") (pintype "passive"))
      (node (ref "D7") (pin "K") (pinfunction "C_K") (pintype "passive"))
    )
    (net (code "64") (name "Net-(D8-C)") (class "Default")
      (node (ref "CON4") (pin "1") (pinfunction "1_1") (pintype "passive"))
      (node (ref "D8") (pin "K") (pinfunction "C_K") (pintype "passive"))
    )
    (net (code "65") (name "Net-(D9-C)") (class "Default")
      (node (ref "CON5") (pin "5") (pinfunction "5_5") (pintype "passive"))
      (node (ref "D9") (pin "K") (pinfunction "C_K") (pintype "passive"))
    )
    (net (code "66") (name "Net-(D11-C)") (class "Default")
      (node (ref "CON5") (pin "1") (pinfunction "1_1") (pintype "passive"))
      (node (ref "D11") (pin "K") (pinfunction "C_K") (pintype "passive"))
    )
    (net (code "67") (name "Net-(D11-PadA)") (class "Default")
      (node (ref "D11") (pin "A") (pinfunction "A_A") (pintype "passive"))
      (node (ref "D13") (pin "A") (pinfunction "A_A") (pintype "passive"))
      (node (ref "D15") (pin "A") (pinfunction "A_A") (pintype "passive"))
      (node (ref "D17") (pin "A") (pinfunction "A_A") (pintype "passive"))
    )
    (net (code "68") (name "Net-(D12-C)") (class "Default")
      (node (ref "CON6") (pin "5") (pinfunction "5_5") (pintype "passive"))
      (node (ref "D12") (pin "K") (pinfunction "C_K") (pintype "passive"))
    )
    (net (code "69") (name "Net-(D12-PadA)") (class "Default")
      (node (ref "D12") (pin "A") (pinfunction "A_A") (pintype "passive"))
      (node (ref "D14") (pin "A") (pinfunction "A_A") (pintype "passive"))
      (node (ref "D16") (pin "A") (pinfunction "A_A") (pintype "passive"))
      (node (ref "D9") (pin "A") (pinfunction "A_A") (pintype "passive"))
    )
    (net (code "70") (name "Net-(D13-C)") (class "Default")
      (node (ref "CON6") (pin "1") (pinfunction "1_1") (pintype "passive"))
      (node (ref "D13") (pin "K") (pinfunction "C_K") (pintype "passive"))
    )
    (net (code "71") (name "Net-(D14-C)") (class "Default")
      (node (ref "CON7") (pin "5") (pinfunction "5_5") (pintype "passive"))
      (node (ref "D14") (pin "K") (pinfunction "C_K") (pintype "passive"))
    )
    (net (code "72") (name "Net-(D15-C)") (class "Default")
      (node (ref "CON7") (pin "1") (pinfunction "1_1") (pintype "passive"))
      (node (ref "D15") (pin "K") (pinfunction "C_K") (pintype "passive"))
    )
    (net (code "73") (name "Net-(D16-C)") (class "Default")
      (node (ref "CON8") (pin "5") (pinfunction "5_5") (pintype "passive"))
      (node (ref "D16") (pin "K") (pinfunction "C_K") (pintype "passive"))
    )
    (net (code "74") (name "Net-(D17-C)") (class "Default")
      (node (ref "CON8") (pin "1") (pinfunction "1_1") (pintype "passive"))
      (node (ref "D17") (pin "K") (pinfunction "C_K") (pintype "passive"))
    )
    (net (code "75") (name "Net-(F3-2)") (class "Default")
      (node (ref "CON20") (pin "1") (pinfunction "1_1") (pintype "passive"))
      (node (ref "CON20") (pin "3") (pinfunction "3_3") (pintype "passive"))
      (node (ref "F3") (pin "P$2") (pinfunction "2_P$2") (pintype "passive"))
      (node (ref "R18") (pin "2") (pinfunction "2_2") (pintype "passive"))
      (node (ref "R3") (pin "2") (pinfunction "2_2") (pintype "passive"))
      (node (ref "R3") (pin "22") (pinfunction "2_22") (pintype "passive"))
    )
    (net (code "76") (name "Net-(IC1-COMP)") (class "Default")
      (node (ref "C1") (pin "2") (pinfunction "2_2") (pintype "passive"))
      (node (ref "C14") (pin "2") (pinfunction "2_2") (pintype "passive"))
      (node (ref "IC1") (pin "4") (pinfunction "COMP_4") (pintype "passive"))
    )
    (net (code "77") (name "Net-(IC1-FB)") (class "Default")
      (node (ref "IC1") (pin "5") (pinfunction "FB_5") (pintype "passive"))
      (node (ref "R22") (pin "2") (pinfunction "2_2") (pintype "passive"))
      (node (ref "R23") (pin "1") (pinfunction "1_1") (pintype "passive"))
    )
    (net (code "78") (name "Net-(IC1-OUT)") (class "Default")
      (node (ref "D18") (pin "C") (pinfunction "C_C") (pintype "passive"))
      (node (ref "IC1") (pin "1") (pinfunction "OUT_1") (pintype "passive"))
      (node (ref "L1") (pin "1") (pinfunction "1_1") (pintype "passive"))
    )
    (net (code "79") (name "Net-(IC1-VREF)") (class "Default")
      (node (ref "IC1") (pin "6") (pinfunction "VREF_6") (pintype "passive"))
      (node (ref "PAJ2") (pin "MB") (pinfunction "1_MB") (pintype "passive"))
    )
    (net (code "80") (name "Net-(IC2-A)") (class "Default")
      (node (ref "IC2") (pin "6") (pinfunction "A_6") (pintype "output"))
      (node (ref "R45") (pin "1") (pinfunction "1_1") (pintype "passive"))
      (node (ref "R48") (pin "2") (pinfunction "2_2") (pintype "passive"))
    )
    (net (code "81") (name "Net-(IC2-B)") (class "Default")
      (node (ref "IC2") (pin "7") (pinfunction "B_7") (pintype "output"))
      (node (ref "R46") (pin "1") (pinfunction "1_1") (pintype "passive"))
      (node (ref "R49") (pin "1") (pinfunction "1_1") (pintype "passive"))
    )
    (net (code "82") (name "Net-(IC2-DE)") (class "Default")
      (node (ref "IC2") (pin "2") (pinfunction "~{RE}_2") (pintype "input"))
      (node (ref "IC2") (pin "3") (pinfunction "DE_3") (pintype "input"))
      (node (ref "R51") (pin "1") (pinfunction "1_1") (pintype "passive"))
    )
    (net (code "83") (name "Net-(IC2-DI)") (class "Default")
      (node (ref "C25") (pin "1") (pinfunction "1_1") (pintype "passive"))
      (node (ref "IC2") (pin "4") (pinfunction "DI_4") (pintype "input"))
      (node (ref "R53") (pin "1") (pinfunction "1_1") (pintype "passive"))
    )
    (net (code "84") (name "Net-(IC2-RO)") (class "Default")
      (node (ref "IC2") (pin "1") (pinfunction "RO_1") (pintype "output"))
      (node (ref "R50") (pin "1") (pinfunction "1_1") (pintype "passive"))
    )
    (net (code "85") (name "Net-(IC3-I1)") (class "Default")
      (node (ref "IC3") (pin "1") (pinfunction "I1_1") (pintype "input"))
      (node (ref "IC4") (pin "4") (pinfunction "Q1_4") (pintype "output"))
    )
    (net (code "86") (name "Net-(IC3-I2)") (class "Default")
      (node (ref "IC3") (pin "2") (pinfunction "I2_2") (pintype "input"))
      (node (ref "IC4") (pin "5") (pinfunction "Q2_5") (pintype "output"))
    )
    (net (code "87") (name "Net-(IC3-I3)") (class "Default")
      (node (ref "IC3") (pin "3") (pinfunction "I3_3") (pintype "input"))
      (node (ref "IC4") (pin "6") (pinfunction "Q3_6") (pintype "output"))
    )
    (net (code "88") (name "Net-(IC3-I4)") (class "Default")
      (node (ref "IC3") (pin "4") (pinfunction "I4_4") (pintype "input"))
      (node (ref "IC4") (pin "7") (pinfunction "Q4_7") (pintype "output"))
    )
    (net (code "89") (name "Net-(IC3-I5)") (class "Default")
      (node (ref "IC3") (pin "5") (pinfunction "I5_5") (pintype "input"))
      (node (ref "IC4") (pin "14") (pinfunction "Q5_14") (pintype "output"))
    )
    (net (code "90") (name "Net-(IC3-I6)") (class "Default")
      (node (ref "IC3") (pin "6") (pinfunction "I6_6") (pintype "input"))
      (node (ref "IC4") (pin "13") (pinfunction "Q6_13") (pintype "output"))
    )
    (net (code "91") (name "Net-(IC3-I7)") (class "Default")
      (node (ref "IC3") (pin "7") (pinfunction "I7_7") (pintype "input"))
      (node (ref "IC4") (pin "12") (pinfunction "Q7_12") (pintype "output"))
    )
    (net (code "92") (name "Net-(IC3-I8)") (class "Default")
      (node (ref "IC3") (pin "8") (pinfunction "I8_8") (pintype "input"))
      (node (ref "IC4") (pin "11") (pinfunction "Q8_11") (pintype "output"))
    )
    (net (code "93") (name "Net-(IC7-RST)") (class "Default")
      (node (ref "IC7") (pin "3") (pinfunction "RST_3") (pintype "output"))
      (node (ref "R34") (pin "1") (pinfunction "1_1") (pintype "passive"))
      (node (ref "R47") (pin "1") (pinfunction "1_1") (pintype "passive"))
      (node (ref "TP10") (pin "MB") (pinfunction "1_MB") (pintype "passive"))
    )
    (net (code "94") (name "Net-(IC7-RST{slash})") (class "Default")
      (node (ref "IC7") (pin "1") (pinfunction "RST/_1") (pintype "output"))
      (node (ref "R29") (pin "1") (pinfunction "1_1") (pintype "passive"))
    )
    (net (code "95") (name "Net-(IC7-VCC)") (class "Default")
      (node (ref "C32") (pin "2") (pinfunction "2_2") (pintype "passive"))
      (node (ref "C33") (pin "2") (pinfunction "2_2") (pintype "passive"))
      (node (ref "IC7") (pin "5") (pinfunction "VCC_5") (pintype "power_in"))
      (node (ref "L3") (pin "1") (pinfunction "1_1") (pintype "passive"))
      (node (ref "TP8") (pin "MB") (pinfunction "1_MB") (pintype "passive"))
    )
    (net (code "96") (name "Net-(OK1A-AC1)") (class "Default")
      (node (ref "OK1") (pin "1") (pinfunction "AC1_1") (pintype "passive"))
      (node (ref "R2") (pin "2") (pinfunction "2_2") (pintype "passive"))
      (node (ref "R2") (pin "22") (pinfunction "2_22") (pintype "passive"))
    )
    (net (code "97") (name "Net-(OK1A-AC2)") (class "Default")
      (node (ref "OK1") (pin "2") (pinfunction "AC2_2") (pintype "passive"))
      (node (ref "R3") (pin "1") (pinfunction "1_1") (pintype "passive"))
      (node (ref "R3") (pin "11") (pinfunction "1_11") (pintype "passive"))
    )
    (net (code "98") (name "Net-(OK1B-AC1)") (class "Default")
      (node (ref "OK1") (pin "3") (pinfunction "AC1_3") (pintype "passive"))
      (node (ref "R4") (pin "2") (pinfunction "2_2") (pintype "passive"))
      (node (ref "R4") (pin "22") (pinfunction "2_22") (pintype "passive"))
    )
    (net (code "99") (name "Net-(OK1B-AC2)") (class "Default")
      (node (ref "OK1") (pin "4") (pinfunction "AC2_4") (pintype "passive"))
      (node (ref "R5") (pin "1") (pinfunction "1_1") (pintype "passive"))
      (node (ref "R5") (pin "11") (pinfunction "1_11") (pintype "passive"))
    )
    (net (code "100") (name "Net-(OK1C-AC1)") (class "Default")
      (node (ref "OK1") (pin "5") (pinfunction "AC1_5") (pintype "passive"))
      (node (ref "R6") (pin "2") (pinfunction "2_2") (pintype "passive"))
      (node (ref "R6") (pin "22") (pinfunction "2_22") (pintype "passive"))
    )
    (net (code "101") (name "Net-(OK1C-AC2)") (class "Default")
      (node (ref "OK1") (pin "6") (pinfunction "AC2_6") (pintype "passive"))
      (node (ref "R7") (pin "1") (pinfunction "1_1") (pintype "passive"))
      (node (ref "R7") (pin "11") (pinfunction "1_11") (pintype "passive"))
    )
    (net (code "102") (name "Net-(OK1D-AC1)") (class "Default")
      (node (ref "OK1") (pin "7") (pinfunction "AC1_7") (pintype "passive"))
      (node (ref "R8") (pin "2") (pinfunction "2_2") (pintype "passive"))
      (node (ref "R8") (pin "22") (pinfunction "2_22") (pintype "passive"))
    )
    (net (code "103") (name "Net-(OK1D-AC2)") (class "Default")
      (node (ref "OK1") (pin "8") (pinfunction "AC2_8") (pintype "passive"))
      (node (ref "R9") (pin "1") (pinfunction "1_1") (pintype "passive"))
      (node (ref "R9") (pin "11") (pinfunction "1_11") (pintype "passive"))
    )
    (net (code "104") (name "Net-(OK2A-AC1)") (class "Default")
      (node (ref "OK2") (pin "1") (pinfunction "AC1_1") (pintype "passive"))
      (node (ref "R10") (pin "2") (pinfunction "2_2") (pintype "passive"))
      (node (ref "R10") (pin "22") (pinfunction "2_22") (pintype "passive"))
    )
    (net (code "105") (name "Net-(OK2A-AC2)") (class "Default")
      (node (ref "OK2") (pin "2") (pinfunction "AC2_2") (pintype "passive"))
      (node (ref "R11") (pin "1") (pinfunction "1_1") (pintype "passive"))
      (node (ref "R11") (pin "11") (pinfunction "1_11") (pintype "passive"))
    )
    (net (code "106") (name "Net-(OK2B-AC1)") (class "Default")
      (node (ref "OK2") (pin "3") (pinfunction "AC1_3") (pintype "passive"))
      (node (ref "R12") (pin "2") (pinfunction "2_2") (pintype "passive"))
      (node (ref "R12") (pin "22") (pinfunction "2_22") (pintype "passive"))
    )
    (net (code "107") (name "Net-(OK2B-AC2)") (class "Default")
      (node (ref "OK2") (pin "4") (pinfunction "AC2_4") (pintype "passive"))
      (node (ref "R13") (pin "1") (pinfunction "1_1") (pintype "passive"))
      (node (ref "R13") (pin "11") (pinfunction "1_11") (pintype "passive"))
    )
    (net (code "108") (name "Net-(OK2C-AC1)") (class "Default")
      (node (ref "OK2") (pin "5") (pinfunction "AC1_5") (pintype "passive"))
      (node (ref "R14") (pin "2") (pinfunction "2_2") (pintype "passive"))
      (node (ref "R14") (pin "22") (pinfunction "2_22") (pintype "passive"))
    )
    (net (code "109") (name "Net-(OK2C-AC2)") (class "Default")
      (node (ref "OK2") (pin "6") (pinfunction "AC2_6") (pintype "passive"))
      (node (ref "R15") (pin "1") (pinfunction "1_1") (pintype "passive"))
      (node (ref "R15") (pin "11") (pinfunction "1_11") (pintype "passive"))
    )
    (net (code "110") (name "Net-(OK2D-AC1)") (class "Default")
      (node (ref "OK2") (pin "7") (pinfunction "AC1_7") (pintype "passive"))
      (node (ref "R16") (pin "2") (pinfunction "2_2") (pintype "passive"))
      (node (ref "R16") (pin "22") (pinfunction "2_22") (pintype "passive"))
    )
    (net (code "111") (name "Net-(OK2D-AC2)") (class "Default")
      (node (ref "OK2") (pin "8") (pinfunction "AC2_8") (pintype "passive"))
      (node (ref "R17") (pin "1") (pinfunction "1_1") (pintype "passive"))
      (node (ref "R17") (pin "11") (pinfunction "1_11") (pintype "passive"))
    )
    (net (code "112") (name "Net-(OK9-AC1)") (class "Default")
      (node (ref "OK9") (pin "1") (pinfunction "AC1_1") (pintype "passive"))
      (node (ref "R40") (pin "2") (pinfunction "2_2") (pintype "passive"))
    )
    (net (code "113") (name "Net-(OK9-AC2)") (class "Default")
      (node (ref "OK9") (pin "2") (pinfunction "AC2_2") (pintype "passive"))
      (node (ref "R28") (pin "2") (pinfunction "2_2") (pintype "passive"))
    )
    (net (code "114") (name "Net-(Q1-G)") (class "Default")
      (node (ref "Q1") (pin "1") (pinfunction "G_1") (pintype "passive"))
      (node (ref "R32") (pin "1") (pinfunction "1_1") (pintype "passive"))
      (node (ref "R36") (pin "1") (pinfunction "1_1") (pintype "passive"))
    )
    (net (code "115") (name "Net-(Q1-S)") (class "Default")
      (node (ref "C12") (pin "+") (pinfunction "+_+") (pintype "passive"))
      (node (ref "Q1") (pin "3") (pinfunction "S_3") (pintype "passive"))
      (node (ref "R31") (pin "1") (pinfunction "1_1") (pintype "passive"))
      (node (ref "R32") (pin "2") (pinfunction "2_2") (pintype "passive"))
    )
    (net (code "116") (name "Net-(Q2-B)") (class "Default")
      (node (ref "Q2") (pin "1") (pinfunction "B_1") (pintype "passive"))
      (node (ref "R38") (pin "2") (pinfunction "2_2") (pintype "passive"))
    )
    (net (code "117") (name "Net-(Q2-C)") (class "Default")
      (node (ref "Q2") (pin "3") (pinfunction "C_3") (pintype "passive"))
      (node (ref "R36") (pin "2") (pinfunction "2_2") (pintype "passive"))
    )
    (net (code "118") (name "Net-(Q3-G)") (class "Default")
      (node (ref "Q3") (pin "1") (pinfunction "G_1") (pintype "passive"))
      (node (ref "R42") (pin "1") (pinfunction "1_1") (pintype "passive"))
      (node (ref "R43") (pin "1") (pinfunction "1_1") (pintype "passive"))
    )
    (net (code "119") (name "Net-(Q3-S)") (class "Default")
      (node (ref "C13") (pin "+") (pinfunction "+_+") (pintype "passive"))
      (node (ref "Q3") (pin "3") (pinfunction "S_3") (pintype "passive"))
      (node (ref "R41") (pin "1") (pinfunction "1_1") (pintype "passive"))
      (node (ref "R42") (pin "2") (pinfunction "2_2") (pintype "passive"))
    )
    (net (code "120") (name "Net-(Q4-B)") (class "Default")
      (node (ref "Q4") (pin "1") (pinfunction "B_1") (pintype "passive"))
      (node (ref "R47") (pin "2") (pinfunction "2_2") (pintype "passive"))
    )
    (net (code "121") (name "Net-(Q4-C)") (class "Default")
      (node (ref "Q4") (pin "3") (pinfunction "C_3") (pintype "passive"))
      (node (ref "R33") (pin "1") (pinfunction "1_1") (pintype "passive"))
    )
    (net (code "122") (name "Net-(Q5-D)") (class "Default")
      (node (ref "L4") (pin "2") (pinfunction "2_2") (pintype "passive"))
      (node (ref "Q5") (pin "3") (pinfunction "D_3") (pintype "passive"))
      (node (ref "R33") (pin "2") (pinfunction "2_2") (pintype "passive"))
      (node (ref "TP12") (pin "MB") (pinfunction "1_MB") (pintype "passive"))
    )
    (net (code "123") (name "Net-(Q5-G)") (class "Default")
      (node (ref "C4") (pin "2") (pinfunction "2_2") (pintype "passive"))
      (node (ref "Q5") (pin "1") (pinfunction "G_1") (pintype "passive"))
      (node (ref "R34") (pin "2") (pinfunction "2_2") (pintype "passive"))
      (node (ref "TP13") (pin "MB") (pinfunction "1_MB") (pintype "passive"))
    )
    (net (code "124") (name "Net-(Q6-PadB)") (class "Default")
      (node (ref "Q6") (pin "B") (pinfunction "B_B") (pintype "passive"))
      (node (ref "R56") (pin "2") (pinfunction "2_2") (pintype "passive"))
    )
    (net (code "125") (name "Net-(Q6-PadC)") (class "Default")
      (node (ref "Q6") (pin "C") (pinfunction "C_C") (pintype "passive"))
      (node (ref "R57") (pin "1") (pinfunction "1_1") (pintype "passive"))
    )
    (net (code "126") (name "Net-(Q7-PadB)") (class "Default")
      (node (ref "Q7") (pin "B") (pinfunction "B_B") (pintype "passive"))
      (node (ref "R54") (pin "2") (pinfunction "2_2") (pintype "passive"))
    )
    (net (code "127") (name "Net-(Q7-PadC)") (class "Default")
      (node (ref "Q7") (pin "C") (pinfunction "C_C") (pintype "passive"))
      (node (ref "R55") (pin "1") (pinfunction "1_1") (pintype "passive"))
    )
    (net (code "128") (name "Net-(Q8-B)") (class "Default")
      (node (ref "Q8") (pin "1") (pinfunction "B_1") (pintype "passive"))
      (node (ref "R44") (pin "2") (pinfunction "2_2") (pintype "passive"))
    )
    (net (code "129") (name "Net-(Q8-C)") (class "Default")
      (node (ref "Q8") (pin "3") (pinfunction "C_3") (pintype "passive"))
      (node (ref "R43") (pin "2") (pinfunction "2_2") (pintype "passive"))
    )
    (net (code "130") (name "Net-(R27-Pad1)") (class "Default")
      (node (ref "R27") (pin "1") (pinfunction "1_1") (pintype "passive"))
      (node (ref "VR1") (pin "1") (pinfunction "1_1") (pintype "passive"))
    )
    (net (code "131") (name "Net-(R27-Pad2)") (class "Default")
      (node (ref "R27") (pin "2") (pinfunction "2_2") (pintype "passive"))
      (node (ref "R28") (pin "1") (pinfunction "1_1") (pintype "passive"))
    )
    (net (code "132") (name "Net-(R39-Pad1)") (class "Default")
      (node (ref "R39") (pin "1") (pinfunction "1_1") (pintype "passive"))
      (node (ref "VR1") (pin "2") (pinfunction "2_2") (pintype "passive"))
    )
    (net (code "133") (name "Net-(R39-Pad2)") (class "Default")
      (node (ref "R39") (pin "2") (pinfunction "2_2") (pintype "passive"))
      (node (ref "R40") (pin "1") (pinfunction "1_1") (pintype "passive"))
    )
    (net (code "134") (name "Net-(TBU1-P$1)") (class "Default")
      (node (ref "R45") (pin "2") (pinfunction "2_2") (pintype "passive"))
      (node (ref "TBU1") (pin "1") (pinfunction "P$1_1") (pintype "passive"))
      (node (ref "TVS1") (pin "1") (pinfunction "1_1") (pintype "passive"))
    )
    (net (code "135") (name "Net-(TBU2-P$1)") (class "Default")
      (node (ref "R46") (pin "2") (pinfunction "2_2") (pintype "passive"))
      (node (ref "TBU2") (pin "1") (pinfunction "P$1_1") (pintype "passive"))
      (node (ref "TVS1") (pin "2") (pinfunction "2_2") (pintype "passive"))
    )
    (net (code "136") (name "V+") (class "Default")
      (node (ref "C2") (pin "1") (pinfunction "1_1") (pintype "passive"))
      (node (ref "C35") (pin "1") (pinfunction "1_1") (pintype "passive"))
      (node (ref "F2") (pin "P$2") (pinfunction "2_P$2") (pintype "passive"))
      (node (ref "F3") (pin "P$1") (pinfunction "1_P$1") (pintype "passive"))
      (node (ref "IC1") (pin "8") (pinfunction "VCC_8") (pintype "passive"))
      (node (ref "IC3") (pin "10") (pinfunction "CD+_10") (pintype "passive"))
      (node (ref "R31") (pin "2") (pinfunction "2_2") (pintype "passive"))
      (node (ref "R41") (pin "2") (pinfunction "2_2") (pintype "passive"))
    )
    (net (code "137") (name "unconnected-(CON1-Pad2)") (class "Default")
      (node (ref "CON1") (pin "2") (pinfunction "2_2") (pintype "passive"))
    )
    (net (code "138") (name "unconnected-(CON1-Pad4)") (class "Default")
      (node (ref "CON1") (pin "4") (pinfunction "4_4") (pintype "passive"))
    )
    (net (code "139") (name "unconnected-(CON2-Pad2)") (class "Default")
      (node (ref "CON2") (pin "2") (pinfunction "2_2") (pintype "passive"))
    )
    (net (code "140") (name "unconnected-(CON2-Pad4)") (class "Default")
      (node (ref "CON2") (pin "4") (pinfunction "4_4") (pintype "passive"))
    )
    (net (code "141") (name "unconnected-(CON3-Pad2)") (class "Default")
      (node (ref "CON3") (pin "2") (pinfunction "2_2") (pintype "passive"))
    )
    (net (code "142") (name "unconnected-(CON3-Pad4)") (class "Default")
      (node (ref "CON3") (pin "4") (pinfunction "4_4") (pintype "passive"))
    )
    (net (code "143") (name "unconnected-(CON4-Pad2)") (class "Default")
      (node (ref "CON4") (pin "2") (pinfunction "2_2") (pintype "passive"))
    )
    (net (code "144") (name "unconnected-(CON4-Pad4)") (class "Default")
      (node (ref "CON4") (pin "4") (pinfunction "4_4") (pintype "passive"))
    )
    (net (code "145") (name "unconnected-(CON5-Pad2)") (class "Default")
      (node (ref "CON5") (pin "2") (pinfunction "2_2") (pintype "passive"))
    )
    (net (code "146") (name "unconnected-(CON5-Pad4)") (class "Default")
      (node (ref "CON5") (pin "4") (pinfunction "4_4") (pintype "passive"))
    )
    (net (code "147") (name "unconnected-(CON6-Pad2)") (class "Default")
      (node (ref "CON6") (pin "2") (pinfunction "2_2") (pintype "passive"))
    )
    (net (code "148") (name "unconnected-(CON6-Pad4)") (class "Default")
      (node (ref "CON6") (pin "4") (pinfunction "4_4") (pintype "passive"))
    )
    (net (code "149") (name "unconnected-(CON7-Pad2)") (class "Default")
      (node (ref "CON7") (pin "2") (pinfunction "2_2") (pintype "passive"))
    )
    (net (code "150") (name "unconnected-(CON7-Pad4)") (class "Default")
      (node (ref "CON7") (pin "4") (pinfunction "4_4") (pintype "passive"))
    )
    (net (code "151") (name "unconnected-(CON8-Pad2)") (class "Default")
      (node (ref "CON8") (pin "2") (pinfunction "2_2") (pintype "passive"))
    )
    (net (code "152") (name "unconnected-(CON8-Pad4)") (class "Default")
      (node (ref "CON8") (pin "4") (pinfunction "4_4") (pintype "passive"))
    )
    (net (code "153") (name "unconnected-(IC1-SYNC-Pad2)") (class "Default")
      (node (ref "IC1") (pin "2") (pinfunction "SYNC_2") (pintype "passive"))
    )
    (net (code "154") (name "unconnected-(IC4A-QS-Pad9)") (class "Default")
      (node (ref "IC4") (pin "9") (pinfunction "QS_9") (pintype "output"))
    )
    (net (code "155") (name "unconnected-(U$1-Pad3.3V)") (class "Default")
      (node (ref "U$1") (pin "3.3V") (pinfunction "3.3V_3.3V") (pintype "bidirectional"))
    )
    (net (code "156") (name "unconnected-(U$1-PadAREF)") (class "Default")
      (node (ref "U$1") (pin "AREF") (pinfunction "AREF_AREF") (pintype "bidirectional"))
    )
    (net (code "157") (name "unconnected-(U$1-PadD8)") (class "Default")
      (node (ref "U$1") (pin "D8") (pinfunction "D8_D8") (pintype "bidirectional"))
    )
    (net (code "158") (name "unconnected-(U$1-PadD9)") (class "Default")
      (node (ref "U$1") (pin "D9") (pinfunction "D9_D9") (pintype "bidirectional"))
    )
    (net (code "159") (name "unconnected-(U$1-PadICSP1)") (class "Default")
      (node (ref "U$1") (pin "ICSP1") (pinfunction "ICSP1_ICSP1") (pintype "bidirectional"))
    )
    (net (code "160") (name "unconnected-(U$1-PadICSP2)") (class "Default")
      (node (ref "U$1") (pin "ICSP2") (pinfunction "ICSP2_ICSP2") (pintype "bidirectional"))
    )
    (net (code "161") (name "unconnected-(U$1-PadICSP3)") (class "Default")
      (node (ref "U$1") (pin "ICSP3") (pinfunction "ICSP3_ICSP3") (pintype "bidirectional"))
    )
    (net (code "162") (name "unconnected-(U$1-PadICSP4)") (class "Default")
      (node (ref "U$1") (pin "ICSP4") (pinfunction "ICSP4_ICSP4") (pintype "bidirectional"))
    )
    (net (code "163") (name "unconnected-(U$1-PadICSP5)") (class "Default")
      (node (ref "U$1") (pin "ICSP5") (pinfunction "ICSP5_ICSP5") (pintype "bidirectional"))
    )
    (net (code "164") (name "unconnected-(U$1-PadICSP6)") (class "Default")
      (node (ref "U$1") (pin "ICSP6") (pinfunction "ICSP6_ICSP6") (pintype "bidirectional"))
    )
    (net (code "165") (name "unconnected-(U$1-PadRAW)") (class "Default")
      (node (ref "U$1") (pin "RAW") (pinfunction "RAW_RAW") (pintype "bidirectional"))
    )
  )
)
